# CameraSmartWatch.net
KiCad netlist of a schematic drawn in EasyEDA Pro
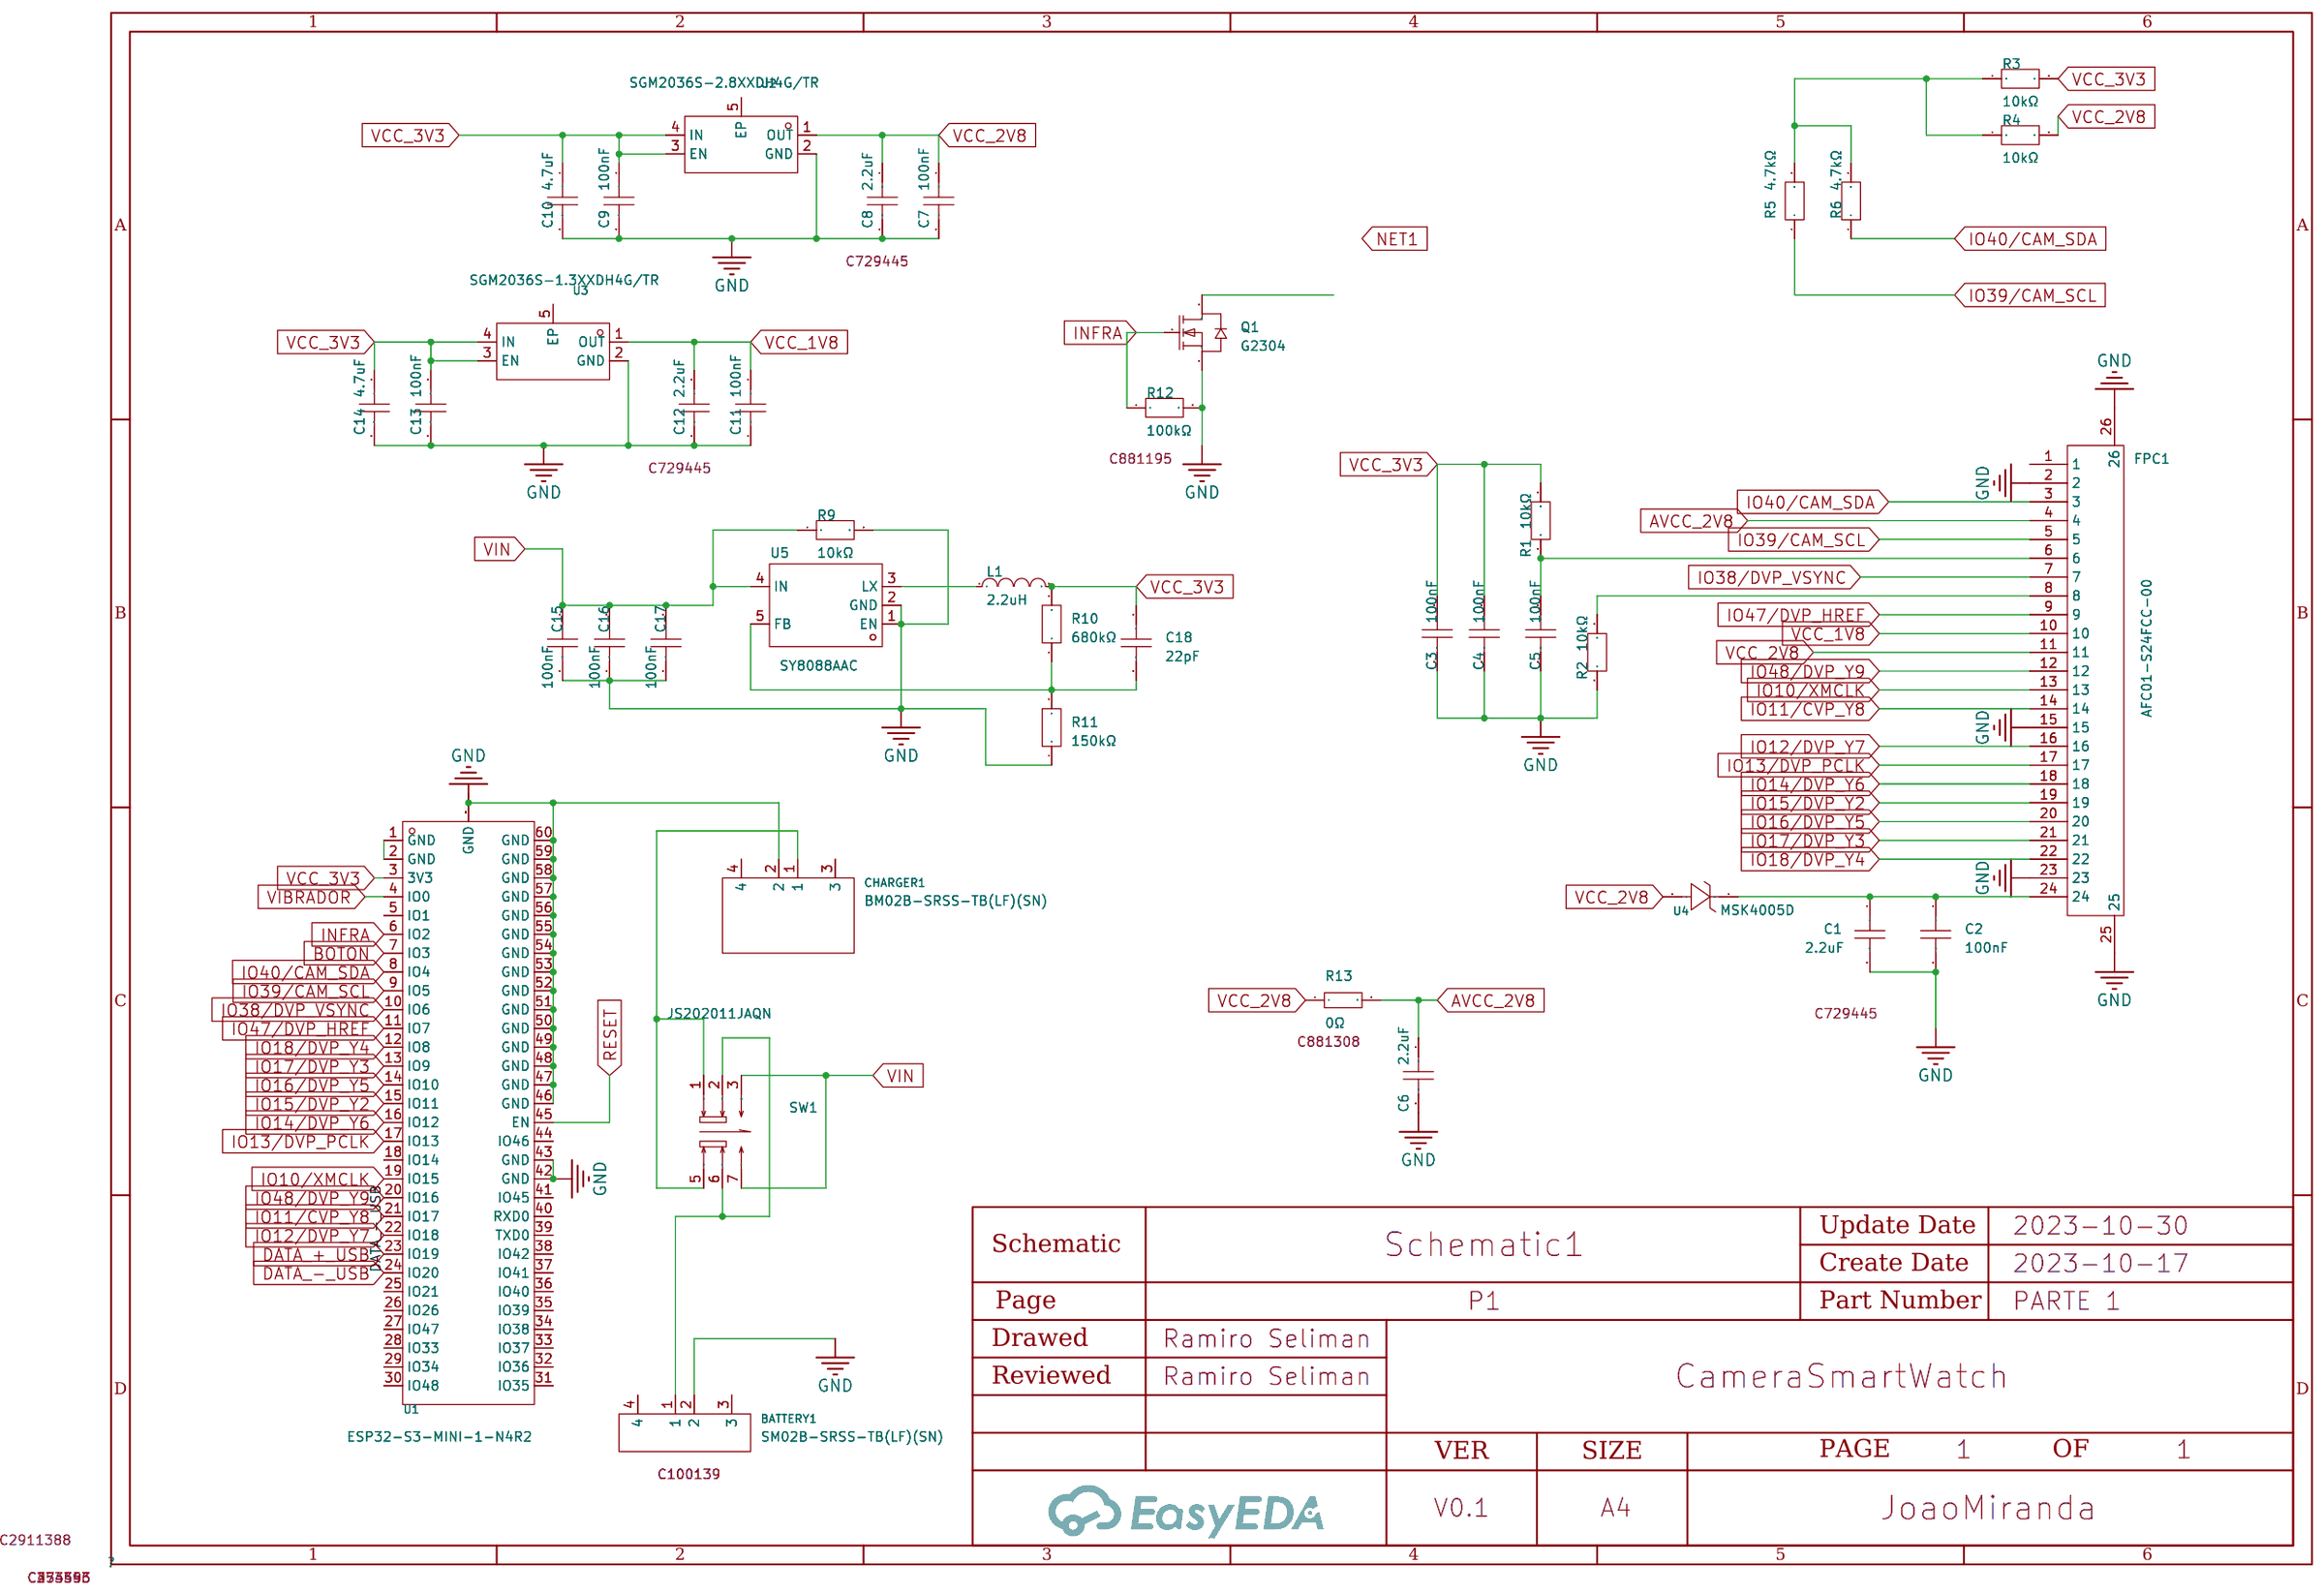
[diagram p0: schematic sheet]

(export (version "E")
  (design (tool "Eeschema 10.0.6"))
  (components
    (comp (ref "BATTERY1")
      (value "SM02B-SRSS-TB(LF)(SN)")
      (footprint "easyedapro:CONN-SMD_2P-P1.00_SM02B-SRSS-TB-LF-SN")
      (fields (field (name "Manufacturer") "JST"))
      (libsource (lib "easyedapro") (part "SM02B-SRSS-TB (LF)(SN)"))
    )
    (comp (ref "C1")
      (value "2.2uF")
      (footprint "easyedapro:C0201")
      (fields
        (field (name "Manufacturer Part") "C0201X5R225M100NT")
        (field (name "Manufacturer") "SANYEAR(叁叶源)")
        (field (name "Supplier Part") "C729445")
      )
      (libsource (lib "easyedapro") (part "CAP"))
    )
    (comp (ref "C2")
      (value "100nF")
      (footprint "easyedapro:C0201")
      (fields
        (field (name "Manufacturer Part") "C0201B104K016TSF")
        (field (name "Manufacturer") "IHHEC(禾伸堂)")
      )
      (libsource (lib "easyedapro") (part "CAP"))
    )
    (comp (ref "C3")
      (value "100nF")
      (footprint "easyedapro:C0201")
      (fields
        (field (name "Manufacturer Part") "C0201B104K016TSF")
        (field (name "Manufacturer") "IHHEC(禾伸堂)")
      )
      (libsource (lib "easyedapro") (part "CAP"))
    )
    (comp (ref "C4")
      (value "100nF")
      (footprint "easyedapro:C0201")
      (fields
        (field (name "Manufacturer Part") "C0201B104K016TSF")
        (field (name "Manufacturer") "IHHEC(禾伸堂)")
      )
      (libsource (lib "easyedapro") (part "CAP"))
    )
    (comp (ref "C5")
      (value "100nF")
      (footprint "easyedapro:C0201")
      (fields
        (field (name "Manufacturer Part") "C0201B104K016TSF")
        (field (name "Manufacturer") "IHHEC(禾伸堂)")
      )
      (libsource (lib "easyedapro") (part "CAP"))
    )
    (comp (ref "C6")
      (value "2.2uF")
      (footprint "easyedapro:C0201")
      (fields
        (field (name "Manufacturer Part") "C0201X5R225M100NT")
        (field (name "Manufacturer") "SANYEAR(叁叶源)")
      )
      (libsource (lib "easyedapro") (part "CAP"))
    )
    (comp (ref "C7")
      (value "100nF")
      (footprint "easyedapro:C0201")
      (fields
        (field (name "Manufacturer Part") "C0201B104K016TSF")
        (field (name "Manufacturer") "IHHEC(禾伸堂)")
      )
      (libsource (lib "easyedapro") (part "CAP"))
    )
    (comp (ref "C8")
      (value "2.2uF")
      (footprint "easyedapro:C0201")
      (fields
        (field (name "Manufacturer Part") "C0201X5R225M100NT")
        (field (name "Manufacturer") "SANYEAR(叁叶源)")
        (field (name "Supplier Part") "C729445")
      )
      (libsource (lib "easyedapro") (part "CAP"))
    )
    (comp (ref "C9")
      (value "100nF")
      (footprint "easyedapro:C0201")
      (fields
        (field (name "Manufacturer Part") "C0201B104K016TSF")
        (field (name "Manufacturer") "IHHEC(禾伸堂)")
      )
      (libsource (lib "easyedapro") (part "CAP"))
    )
    (comp (ref "C10")
      (value "4.7uF")
      (footprint "easyedapro:C0201")
      (fields
        (field (name "Manufacturer Part") "C0402X5R475M250NT")
        (field (name "Manufacturer") "SANYEAR(叁叶源)")
        (field (name "Supplier Part") "C2911388")
      )
      (libsource (lib "easyedapro") (part "CAP"))
    )
    (comp (ref "C11")
      (value "100nF")
      (footprint "easyedapro:C0201")
      (fields
        (field (name "Manufacturer Part") "C0201B104K016TSF")
        (field (name "Manufacturer") "IHHEC(禾伸堂)")
      )
      (libsource (lib "easyedapro") (part "CAP"))
    )
    (comp (ref "C12")
      (value "2.2uF")
      (footprint "easyedapro:C0201")
      (fields
        (field (name "Manufacturer Part") "C0201X5R225M100NT")
        (field (name "Manufacturer") "SANYEAR(叁叶源)")
        (field (name "Supplier Part") "C729445")
      )
      (libsource (lib "easyedapro") (part "CAP"))
    )
    (comp (ref "C13")
      (value "100nF")
      (footprint "easyedapro:C0201")
      (fields
        (field (name "Manufacturer Part") "C0201B104K016TSF")
        (field (name "Manufacturer") "IHHEC(禾伸堂)")
      )
      (libsource (lib "easyedapro") (part "CAP"))
    )
    (comp (ref "C14")
      (value "4.7uF")
      (footprint "easyedapro:C0201")
      (fields
        (field (name "Manufacturer Part") "C0402X5R475M250NT")
        (field (name "Manufacturer") "SANYEAR(叁叶源)")
        (field (name "Supplier Part") "C2911388")
      )
      (libsource (lib "easyedapro") (part "CAP"))
    )
    (comp (ref "C15")
      (value "100nF")
      (footprint "easyedapro:C0201")
      (fields
        (field (name "Manufacturer Part") "C0201B104K016TSF")
        (field (name "Manufacturer") "IHHEC(禾伸堂)")
      )
      (libsource (lib "easyedapro") (part "CAP"))
    )
    (comp (ref "C16")
      (value "100nF")
      (footprint "easyedapro:C0201")
      (fields
        (field (name "Manufacturer Part") "C0201B104K016TSF")
        (field (name "Manufacturer") "IHHEC(禾伸堂)")
      )
      (libsource (lib "easyedapro") (part "CAP"))
    )
    (comp (ref "C17")
      (value "100nF")
      (footprint "easyedapro:C0201")
      (fields
        (field (name "Manufacturer Part") "C0201B104K016TSF")
        (field (name "Manufacturer") "IHHEC(禾伸堂)")
      )
      (libsource (lib "easyedapro") (part "CAP"))
    )
    (comp (ref "C18")
      (value "22pF")
      (footprint "easyedapro:C0201")
      (fields
        (field (name "Manufacturer Part") "CC0201FRNPO8BN220")
        (field (name "Manufacturer") "YAGEO(国巨)")
      )
      (libsource (lib "easyedapro") (part "CAP"))
    )
    (comp (ref "CHARGER1")
      (value "BM02B-SRSS-TB(LF)(SN)")
      (footprint "easyedapro:CONN-TH_BM02B-SRSS-TB-LF-SN")
      (fields (field (name "Manufacturer") "JST"))
      (libsource (lib "easyedapro") (part "BM02B-SRSS-TB (LF)(SN)"))
    )
    (comp (ref "FPC1")
      (value "AFC01-S24FCC-00")
      (footprint "easyedapro:FPC-SMD_P0.5-24P_FGS-XJ-H2.0")
      (fields (field (name "Manufacturer") "JS(钜硕电子)"))
      (libsource (lib "easyedapro") (part "AFC01-S24FCC-00"))
    )
    (comp (ref "L1")
      (value "2.2uH")
      (footprint "easyedapro:L0603")
      (fields
        (field (name "Manufacturer Part") "CKCS252012-2.2uH/N")
        (field (name "Manufacturer") "CENKER(岑科)")
        (field (name "Supplier Part") "C354553")
      )
      (libsource (lib "easyedapro") (part "电感"))
    )
    (comp (ref "Q1")
      (value "G2304")
      (footprint "easyedapro:SOT-23-3_L2.9-W1.3-P1.90-LS2.4-BR")
      (fields (field (name "Manufacturer") "GOFORD(谷峰)"))
      (libsource (lib "easyedapro") (part "G2304"))
    )
    (comp (ref "R1")
      (value "10kΩ")
      (footprint "easyedapro:R0603")
      (description "Type: Resistance: Tolerance:±1% Tolerance:±1% Power(Watts):- Overload Voltage (Max):-")
      (fields (field (name "Manufacturer Part") "CR0201FH1002G") (field (name "Manufacturer") "LIZ(丽智电子)"))
      (libsource (lib "easyedapro") (part "CR0603F0R00P05Z"))
    )
    (comp (ref "R2")
      (value "10kΩ")
      (footprint "easyedapro:R0603")
      (description "Type: Resistance: Tolerance:±1% Tolerance:±1% Power(Watts):- Overload Voltage (Max):-")
      (fields (field (name "Manufacturer Part") "CR0201FH1002G") (field (name "Manufacturer") "LIZ(丽智电子)"))
      (libsource (lib "easyedapro") (part "CR0603F0R00P05Z"))
    )
    (comp (ref "R3")
      (value "10kΩ")
      (footprint "easyedapro:R0603")
      (description "Type: Resistance: Tolerance:±1% Tolerance:±1% Power(Watts):- Overload Voltage (Max):-")
      (fields (field (name "Manufacturer Part") "CR0201FH1002G") (field (name "Manufacturer") "LIZ(丽智电子)"))
      (libsource (lib "easyedapro") (part "CR0603F0R00P05Z"))
    )
    (comp (ref "R4")
      (value "10kΩ")
      (footprint "easyedapro:R0603")
      (description "Type: Resistance: Tolerance:±1% Tolerance:±1% Power(Watts):- Overload Voltage (Max):-")
      (fields (field (name "Manufacturer Part") "CR0201FH1002G") (field (name "Manufacturer") "LIZ(丽智电子)"))
      (libsource (lib "easyedapro") (part "CR0603F0R00P05Z"))
    )
    (comp (ref "R5")
      (value "4.7kΩ")
      (footprint "easyedapro:R0603")
      (fields
        (field (name "Manufacturer Part") "CR0201FH4701G")
        (field (name "Manufacturer") "LIZ(丽智电子)")
        (field (name "Supplier Part") "C100139")
      )
      (libsource (lib "easyedapro") (part "CR0603F0R00P05Z"))
    )
    (comp (ref "R6")
      (value "4.7kΩ")
      (footprint "easyedapro:R0603")
      (fields
        (field (name "Manufacturer Part") "CR0201FH4701G")
        (field (name "Manufacturer") "LIZ(丽智电子)")
        (field (name "Supplier Part") "C100139")
      )
      (libsource (lib "easyedapro") (part "CR0603F0R00P05Z"))
    )
    (comp (ref "R9")
      (value "10kΩ")
      (footprint "easyedapro:R0603")
      (description "Type: Resistance: Tolerance:±1% Tolerance:±1% Power(Watts):- Overload Voltage (Max):-")
      (fields (field (name "Manufacturer Part") "CR0201FH1002G") (field (name "Manufacturer") "LIZ(丽智电子)"))
      (libsource (lib "easyedapro") (part "CR0603F0R00P05Z"))
    )
    (comp (ref "R10")
      (value "680kΩ")
      (footprint "easyedapro:R0603")
      (fields
        (field (name "Manufacturer Part") "0201WMF6803TEE")
        (field (name "Manufacturer") "UNI-ROYAL(厚声)")
        (field (name "Supplier Part") "C473493")
      )
      (libsource (lib "easyedapro") (part "CR0603F0R00P05Z"))
    )
    (comp (ref "R11")
      (value "150kΩ")
      (footprint "easyedapro:R0603")
      (fields
        (field (name "Manufacturer Part") "RC0201FR-07150KL")
        (field (name "Manufacturer") "YAGEO(国巨)")
        (field (name "Supplier Part") "C274346")
      )
      (libsource (lib "easyedapro") (part "CR0603F0R00P05Z"))
    )
    (comp (ref "R12")
      (value "100kΩ")
      (footprint "easyedapro:R0603")
      (fields
        (field (name "Manufacturer Part") "CR0201J100KQ15Z")
        (field (name "Manufacturer") "EVER OHMS(天二科技)")
        (field (name "Supplier Part") "C881195")
      )
      (libsource (lib "easyedapro") (part "CR0603F0R00P05Z"))
    )
    (comp (ref "R13")
      (value "0Ω")
      (footprint "easyedapro:R0603")
      (fields
        (field (name "Manufacturer Part") "CR0603F0R00P05Z")
        (field (name "Manufacturer") "EVER OHMS(天二科技)")
        (field (name "Supplier Part") "C881308")
      )
      (libsource (lib "easyedapro") (part "Res"))
    )
    (comp (ref "SW1")
      (value "JS202011JAQN")
      (footprint "easyedapro:SW-SMD_JS202011JAQN")
      (fields (field (name "Manufacturer") "C&K"))
      (libsource (lib "easyedapro") (part "JS202011JAQN"))
    )
    (comp (ref "U1")
      (value "ESP32-S3-MINI-1-N4R2")
      (footprint "easyedapro:BULETM-SMD_ESP32-S3-MINI-1-N8")
      (fields (field (name "Manufacturer") "ESPRESSIF(乐鑫)"))
      (libsource (lib "easyedapro") (part "ESP32-S3-MINI-1-N4R2"))
    )
    (comp (ref "U2")
      (value "SGM2036S-2.8XXDH4G/TR")
      (footprint "easyedapro:USPQ-4B04_L1.0-W1.0-P0.65-BL-EP")
      (fields (field (name "Manufacturer") "SGMICRO(圣邦微)"))
      (libsource (lib "easyedapro") (part "SGM2036S-2.8XXDH4G/TR"))
    )
    (comp (ref "U3")
      (value "SGM2036S-1.3XXDH4G/TR")
      (footprint "easyedapro:USPQ-4B04_L1.0-W1.0-P0.65-BL-EP")
      (fields (field (name "Manufacturer") "SGMICRO(圣邦微)"))
      (libsource (lib "easyedapro") (part "SGM2036S-2.8XXDH4G/TR"))
    )
    (comp (ref "U4")
      (value "MSK4005D")
      (footprint "easyedapro:SOD-882_L1.0-W0.6-RD")
      (fields (field (name "Manufacturer") "SHIKUES(时科)"))
      (libsource (lib "easyedapro") (part "MSK4005D"))
    )
    (comp (ref "U5")
      (value "SY8088AAC")
      (footprint "easyedapro:SOT-23-5_L3.0-W1.7-P0.95-LS2.8-BR")
      (fields (field (name "Manufacturer") "silergy(矽力杰)"))
      (libsource (lib "easyedapro") (part "SY8088AAC"))
    )
  )
  (nets
    (net (code "1") (name "AVCC_2V8") (class "Default")
      (node (ref "C6") (pin "1") (pinfunction "1_1") (pintype "input"))
      (node (ref "FPC1") (pin "4") (pinfunction "4_4") (pintype "input"))
      (node (ref "R13") (pin "2") (pinfunction "2_2") (pintype "input"))
    )
    (net (code "2") (name "BOTON") (class "Default")
      (node (ref "U1") (pin "7") (pinfunction "IO3_7") (pintype "input"))
    )
    (net (code "3") (name "DATA_+_USB") (class "Default")
      (node (ref "U1") (pin "23") (pinfunction "IO19_23") (pintype "input"))
    )
    (net (code "4") (name "DATA_-_USB") (class "Default")
      (node (ref "U1") (pin "24") (pinfunction "IO20_24") (pintype "input"))
    )
    (net (code "5") (name "GND") (class "Default")
      (node (ref "BATTERY1") (pin "2") (pinfunction "2_2") (pintype "input"))
      (node (ref "C1") (pin "2") (pinfunction "2_2") (pintype "input"))
      (node (ref "C10") (pin "2") (pinfunction "2_2") (pintype "input"))
      (node (ref "C11") (pin "2") (pinfunction "2_2") (pintype "input"))
      (node (ref "C12") (pin "2") (pinfunction "2_2") (pintype "input"))
      (node (ref "C13") (pin "2") (pinfunction "2_2") (pintype "input"))
      (node (ref "C14") (pin "2") (pinfunction "2_2") (pintype "input"))
      (node (ref "C15") (pin "2") (pinfunction "2_2") (pintype "input"))
      (node (ref "C16") (pin "1") (pinfunction "1_1") (pintype "input"))
      (node (ref "C17") (pin "1") (pinfunction "1_1") (pintype "input"))
      (node (ref "C2") (pin "2") (pinfunction "2_2") (pintype "input"))
      (node (ref "C3") (pin "2") (pinfunction "2_2") (pintype "input"))
      (node (ref "C4") (pin "2") (pinfunction "2_2") (pintype "input"))
      (node (ref "C5") (pin "2") (pinfunction "2_2") (pintype "input"))
      (node (ref "C6") (pin "2") (pinfunction "2_2") (pintype "input"))
      (node (ref "C7") (pin "2") (pinfunction "2_2") (pintype "input"))
      (node (ref "C8") (pin "2") (pinfunction "2_2") (pintype "input"))
      (node (ref "C9") (pin "2") (pinfunction "2_2") (pintype "input"))
      (node (ref "CHARGER1") (pin "2") (pinfunction "2_2") (pintype "input"))
      (node (ref "FPC1") (pin "15") (pinfunction "15_15") (pintype "input"))
      (node (ref "FPC1") (pin "2") (pinfunction "2_2") (pintype "input"))
      (node (ref "FPC1") (pin "23") (pinfunction "23_23") (pintype "input"))
      (node (ref "FPC1") (pin "25") (pinfunction "25_25") (pintype "input"))
      (node (ref "FPC1") (pin "26") (pinfunction "26_26") (pintype "input"))
      (node (ref "Q1") (pin "2") (pinfunction "S_2") (pintype "input"))
      (node (ref "R11") (pin "1") (pinfunction "1_1") (pintype "input"))
      (node (ref "R12") (pin "2") (pinfunction "2_2") (pintype "input"))
      (node (ref "R2") (pin "1") (pinfunction "1_1") (pintype "input"))
      (node (ref "R9") (pin "2") (pinfunction "2_2") (pintype "input"))
      (node (ref "U1") (pin "42") (pinfunction "GND_42") (pintype "input"))
      (node (ref "U1") (pin "43") (pinfunction "GND_43") (pintype "input"))
      (node (ref "U1") (pin "46") (pinfunction "GND_46") (pintype "input"))
      (node (ref "U1") (pin "47") (pinfunction "GND_47") (pintype "input"))
      (node (ref "U1") (pin "48") (pinfunction "GND_48") (pintype "input"))
      (node (ref "U1") (pin "49") (pinfunction "GND_49") (pintype "input"))
      (node (ref "U1") (pin "50") (pinfunction "GND_50") (pintype "input"))
      (node (ref "U1") (pin "51") (pinfunction "GND_51") (pintype "input"))
      (node (ref "U1") (pin "52") (pinfunction "GND_52") (pintype "input"))
      (node (ref "U1") (pin "53") (pinfunction "GND_53") (pintype "input"))
      (node (ref "U1") (pin "54") (pinfunction "GND_54") (pintype "input"))
      (node (ref "U1") (pin "55") (pinfunction "GND_55") (pintype "input"))
      (node (ref "U1") (pin "56") (pinfunction "GND_56") (pintype "input"))
      (node (ref "U1") (pin "57") (pinfunction "GND_57") (pintype "input"))
      (node (ref "U1") (pin "58") (pinfunction "GND_58") (pintype "input"))
      (node (ref "U1") (pin "59") (pinfunction "GND_59") (pintype "input"))
      (node (ref "U1") (pin "60") (pinfunction "GND_60") (pintype "input"))
      (node (ref "U1") (pin "GND") (pinfunction "GND_GND") (pintype "input"))
      (node (ref "U2") (pin "2") (pinfunction "GND_2") (pintype "input"))
      (node (ref "U3") (pin "2") (pinfunction "GND_2") (pintype "input"))
      (node (ref "U5") (pin "1") (pinfunction "EN_1") (pintype "input"))
      (node (ref "U5") (pin "2") (pinfunction "GND_2") (pintype "input"))
    )
    (net (code "6") (name "INFRA") (class "Default")
      (node (ref "Q1") (pin "1") (pinfunction "G_1") (pintype "input"))
      (node (ref "R12") (pin "1") (pinfunction "1_1") (pintype "input"))
      (node (ref "U1") (pin "6") (pinfunction "IO2_6") (pintype "input"))
    )
    (net (code "7") (name "IO10{slash}XMCLK") (class "Default")
      (node (ref "FPC1") (pin "13") (pinfunction "13_13") (pintype "input"))
      (node (ref "U1") (pin "19") (pinfunction "IO15_19") (pintype "input"))
    )
    (net (code "8") (name "IO11{slash}CVP_Y8") (class "Default")
      (node (ref "FPC1") (pin "14") (pinfunction "14_14") (pintype "input"))
      (node (ref "U1") (pin "21") (pinfunction "IO17_21") (pintype "input"))
    )
    (net (code "9") (name "IO12{slash}DVP_Y7") (class "Default")
      (node (ref "FPC1") (pin "16") (pinfunction "16_16") (pintype "input"))
      (node (ref "U1") (pin "22") (pinfunction "IO18_22") (pintype "input"))
    )
    (net (code "10") (name "IO13{slash}DVP_PCLK") (class "Default")
      (node (ref "FPC1") (pin "17") (pinfunction "17_17") (pintype "input"))
      (node (ref "U1") (pin "17") (pinfunction "IO13_17") (pintype "input"))
    )
    (net (code "11") (name "IO14{slash}DVP_Y6") (class "Default")
      (node (ref "FPC1") (pin "18") (pinfunction "18_18") (pintype "input"))
      (node (ref "U1") (pin "16") (pinfunction "IO12_16") (pintype "input"))
    )
    (net (code "12") (name "IO15{slash}DVP_Y2") (class "Default")
      (node (ref "FPC1") (pin "19") (pinfunction "19_19") (pintype "input"))
      (node (ref "U1") (pin "15") (pinfunction "IO11_15") (pintype "input"))
    )
    (net (code "13") (name "IO16{slash}DVP_Y5") (class "Default")
      (node (ref "FPC1") (pin "20") (pinfunction "20_20") (pintype "input"))
      (node (ref "U1") (pin "14") (pinfunction "IO10_14") (pintype "input"))
    )
    (net (code "14") (name "IO17{slash}DVP_Y3") (class "Default")
      (node (ref "FPC1") (pin "21") (pinfunction "21_21") (pintype "input"))
      (node (ref "U1") (pin "13") (pinfunction "IO9_13") (pintype "input"))
    )
    (net (code "15") (name "IO18{slash}DVP_Y4") (class "Default")
      (node (ref "FPC1") (pin "22") (pinfunction "22_22") (pintype "input"))
      (node (ref "U1") (pin "12") (pinfunction "IO8_12") (pintype "input"))
    )
    (net (code "16") (name "IO38{slash}DVP_VSYNC") (class "Default")
      (node (ref "FPC1") (pin "7") (pinfunction "7_7") (pintype "input"))
      (node (ref "U1") (pin "10") (pinfunction "IO6_10") (pintype "input"))
    )
    (net (code "17") (name "IO39{slash}CAM_SCL") (class "Default")
      (node (ref "FPC1") (pin "5") (pinfunction "5_5") (pintype "input"))
      (node (ref "R5") (pin "1") (pinfunction "1_1") (pintype "input"))
      (node (ref "U1") (pin "9") (pinfunction "IO5_9") (pintype "input"))
    )
    (net (code "18") (name "IO40{slash}CAM_SDA") (class "Default")
      (node (ref "FPC1") (pin "3") (pinfunction "3_3") (pintype "input"))
      (node (ref "R6") (pin "1") (pinfunction "1_1") (pintype "input"))
      (node (ref "U1") (pin "8") (pinfunction "IO4_8") (pintype "input"))
    )
    (net (code "19") (name "IO47{slash}DVP_HREF") (class "Default")
      (node (ref "FPC1") (pin "9") (pinfunction "9_9") (pintype "input"))
      (node (ref "U1") (pin "11") (pinfunction "IO7_11") (pintype "input"))
    )
    (net (code "20") (name "IO48{slash}DVP_Y9") (class "Default")
      (node (ref "FPC1") (pin "12") (pinfunction "12_12") (pintype "input"))
      (node (ref "U1") (pin "20") (pinfunction "IO16_20") (pintype "input"))
    )
    (net (code "22") (name "Net-(BATTERY1-Pad1)") (class "Default")
      (node (ref "BATTERY1") (pin "1") (pinfunction "1_1") (pintype "input"))
      (node (ref "SW1") (pin "2") (pinfunction "2_2") (pintype "input"))
      (node (ref "SW1") (pin "6") (pinfunction "6_6") (pintype "input"))
    )
    (net (code "23") (name "Net-(C5-Pad1)") (class "Default")
      (node (ref "C5") (pin "1") (pinfunction "1_1") (pintype "input"))
      (node (ref "FPC1") (pin "6") (pinfunction "6_6") (pintype "input"))
      (node (ref "R1") (pin "1") (pinfunction "1_1") (pintype "input"))
    )
    (net (code "24") (name "Net-(CHARGER1-Pad1)") (class "Default")
      (node (ref "CHARGER1") (pin "1") (pinfunction "1_1") (pintype "input"))
      (node (ref "SW1") (pin "1") (pinfunction "1_1") (pintype "input"))
      (node (ref "SW1") (pin "5") (pinfunction "5_5") (pintype "input"))
    )
    (net (code "25") (name "Net-(FPC1-Pad8)") (class "Default")
      (node (ref "FPC1") (pin "8") (pinfunction "8_8") (pintype "input"))
      (node (ref "R2") (pin "2") (pinfunction "2_2") (pintype "input"))
    )
    (net (code "26") (name "Net-(R3-Pad1)") (class "Default")
      (node (ref "R3") (pin "1") (pinfunction "1_1") (pintype "input"))
      (node (ref "R4") (pin "1") (pinfunction "1_1") (pintype "input"))
      (node (ref "R5") (pin "2") (pinfunction "2_2") (pintype "input"))
      (node (ref "R6") (pin "2") (pinfunction "2_2") (pintype "input"))
    )
    (net (code "27") (name "Net-(U1-GND-Pad1)") (class "Default")
      (node (ref "U1") (pin "1") (pinfunction "GND_1") (pintype "input"))
      (node (ref "U1") (pin "2") (pinfunction "GND_2") (pintype "input"))
    )
    (net (code "28") (name "Net-(U4-K)") (class "Default")
      (node (ref "C1") (pin "1") (pinfunction "1_1") (pintype "input"))
      (node (ref "C2") (pin "1") (pinfunction "1_1") (pintype "input"))
      (node (ref "FPC1") (pin "24") (pinfunction "24_24") (pintype "input"))
      (node (ref "U4") (pin "1") (pinfunction "K_1") (pintype "input"))
    )
    (net (code "29") (name "Net-(U5-FB)") (class "Default")
      (node (ref "C18") (pin "2") (pinfunction "2_2") (pintype "input"))
      (node (ref "R10") (pin "1") (pinfunction "1_1") (pintype "input"))
      (node (ref "R11") (pin "2") (pinfunction "2_2") (pintype "input"))
      (node (ref "U5") (pin "5") (pinfunction "FB_5") (pintype "input"))
    )
    (net (code "30") (name "Net-(U5-LX)") (class "Default")
      (node (ref "L1") (pin "1") (pinfunction "1_1") (pintype "input"))
      (node (ref "U5") (pin "3") (pinfunction "LX_3") (pintype "input"))
    )
    (net (code "31") (name "RESET") (class "Default")
      (node (ref "U1") (pin "45") (pinfunction "EN_45") (pintype "input"))
    )
    (net (code "32") (name "VCC_1V8") (class "Default")
      (node (ref "C11") (pin "1") (pinfunction "1_1") (pintype "input"))
      (node (ref "C12") (pin "1") (pinfunction "1_1") (pintype "input"))
      (node (ref "FPC1") (pin "10") (pinfunction "10_10") (pintype "input"))
      (node (ref "U3") (pin "1") (pinfunction "OUT_1") (pintype "input"))
    )
    (net (code "33") (name "VCC_2V8") (class "Default")
      (node (ref "C7") (pin "1") (pinfunction "1_1") (pintype "input"))
      (node (ref "C8") (pin "1") (pinfunction "1_1") (pintype "input"))
      (node (ref "FPC1") (pin "11") (pinfunction "11_11") (pintype "input"))
      (node (ref "R13") (pin "1") (pinfunction "1_1") (pintype "input"))
      (node (ref "R4") (pin "2") (pinfunction "2_2") (pintype "input"))
      (node (ref "U2") (pin "1") (pinfunction "OUT_1") (pintype "input"))
      (node (ref "U4") (pin "2") (pinfunction "A_2") (pintype "input"))
    )
    (net (code "34") (name "VCC_3V3") (class "Default")
      (node (ref "C10") (pin "1") (pinfunction "1_1") (pintype "input"))
      (node (ref "C13") (pin "1") (pinfunction "1_1") (pintype "input"))
      (node (ref "C14") (pin "1") (pinfunction "1_1") (pintype "input"))
      (node (ref "C18") (pin "1") (pinfunction "1_1") (pintype "input"))
      (node (ref "C3") (pin "1") (pinfunction "1_1") (pintype "input"))
      (node (ref "C4") (pin "1") (pinfunction "1_1") (pintype "input"))
      (node (ref "C9") (pin "1") (pinfunction "1_1") (pintype "input"))
      (node (ref "L1") (pin "2") (pinfunction "2_2") (pintype "input"))
      (node (ref "R1") (pin "2") (pinfunction "2_2") (pintype "input"))
      (node (ref "R10") (pin "2") (pinfunction "2_2") (pintype "input"))
      (node (ref "R3") (pin "2") (pinfunction "2_2") (pintype "input"))
      (node (ref "U1") (pin "3") (pinfunction "3V3_3") (pintype "input"))
      (node (ref "U2") (pin "3") (pinfunction "EN_3") (pintype "input"))
      (node (ref "U2") (pin "4") (pinfunction "IN_4") (pintype "input"))
      (node (ref "U3") (pin "3") (pinfunction "EN_3") (pintype "input"))
      (node (ref "U3") (pin "4") (pinfunction "IN_4") (pintype "input"))
    )
    (net (code "35") (name "VIBRADOR") (class "Default")
      (node (ref "U1") (pin "4") (pinfunction "IO0_4") (pintype "input"))
    )
    (net (code "36") (name "VIN") (class "Default")
      (node (ref "C15") (pin "1") (pinfunction "1_1") (pintype "input"))
      (node (ref "C16") (pin "2") (pinfunction "2_2") (pintype "input"))
      (node (ref "C17") (pin "2") (pinfunction "2_2") (pintype "input"))
      (node (ref "R9") (pin "1") (pinfunction "1_1") (pintype "input"))
      (node (ref "SW1") (pin "3") (pinfunction "3_3") (pintype "input"))
      (node (ref "SW1") (pin "7") (pinfunction "7_7") (pintype "input"))
      (node (ref "U5") (pin "4") (pinfunction "IN_4") (pintype "input"))
    )
    (net (code "37") (name "unconnected-(BATTERY1-Pad3)") (class "Default")
      (node (ref "BATTERY1") (pin "3") (pinfunction "3_3") (pintype "input"))
    )
    (net (code "38") (name "unconnected-(BATTERY1-Pad4)") (class "Default")
      (node (ref "BATTERY1") (pin "4") (pinfunction "4_4") (pintype "input"))
    )
    (net (code "39") (name "unconnected-(CHARGER1-Pad3)") (class "Default")
      (node (ref "CHARGER1") (pin "3") (pinfunction "3_3") (pintype "input"))
    )
    (net (code "40") (name "unconnected-(CHARGER1-Pad4)") (class "Default")
      (node (ref "CHARGER1") (pin "4") (pinfunction "4_4") (pintype "input"))
    )
    (net (code "41") (name "unconnected-(FPC1-Pad1)") (class "Default")
      (node (ref "FPC1") (pin "1") (pinfunction "1_1") (pintype "input"))
    )
    (net (code "42") (name "unconnected-(Q1-D-Pad3)") (class "Default")
      (node (ref "Q1") (pin "3") (pinfunction "D_3") (pintype "input"))
    )
    (net (code "43") (name "unconnected-(U1-IO1-Pad5)") (class "Default")
      (node (ref "U1") (pin "5") (pinfunction "IO1_5") (pintype "input"))
    )
    (net (code "44") (name "unconnected-(U1-IO14-Pad18)") (class "Default")
      (node (ref "U1") (pin "18") (pinfunction "IO14_18") (pintype "input"))
    )
    (net (code "45") (name "unconnected-(U1-IO21-Pad25)") (class "Default")
      (node (ref "U1") (pin "25") (pinfunction "IO21_25") (pintype "input"))
    )
    (net (code "46") (name "unconnected-(U1-IO26-Pad26)") (class "Default")
      (node (ref "U1") (pin "26") (pinfunction "IO26_26") (pintype "input"))
    )
    (net (code "47") (name "unconnected-(U1-IO33-Pad28)") (class "Default")
      (node (ref "U1") (pin "28") (pinfunction "IO33_28") (pintype "input"))
    )
    (net (code "48") (name "unconnected-(U1-IO34-Pad29)") (class "Default")
      (node (ref "U1") (pin "29") (pinfunction "IO34_29") (pintype "input"))
    )
    (net (code "49") (name "unconnected-(U1-IO35-Pad31)") (class "Default")
      (node (ref "U1") (pin "31") (pinfunction "IO35_31") (pintype "input"))
    )
    (net (code "50") (name "unconnected-(U1-IO36-Pad32)") (class "Default")
      (node (ref "U1") (pin "32") (pinfunction "IO36_32") (pintype "input"))
    )
    (net (code "51") (name "unconnected-(U1-IO37-Pad33)") (class "Default")
      (node (ref "U1") (pin "33") (pinfunction "IO37_33") (pintype "input"))
    )
    (net (code "52") (name "unconnected-(U1-IO38-Pad34)") (class "Default")
      (node (ref "U1") (pin "34") (pinfunction "IO38_34") (pintype "input"))
    )
    (net (code "53") (name "unconnected-(U1-IO39-Pad35)") (class "Default")
      (node (ref "U1") (pin "35") (pinfunction "IO39_35") (pintype "input"))
    )
    (net (code "54") (name "unconnected-(U1-IO40-Pad36)") (class "Default")
      (node (ref "U1") (pin "36") (pinfunction "IO40_36") (pintype "input"))
    )
    (net (code "55") (name "unconnected-(U1-IO41-Pad37)") (class "Default")
      (node (ref "U1") (pin "37") (pinfunction "IO41_37") (pintype "input"))
    )
    (net (code "56") (name "unconnected-(U1-IO42-Pad38)") (class "Default")
      (node (ref "U1") (pin "38") (pinfunction "IO42_38") (pintype "input"))
    )
    (net (code "57") (name "unconnected-(U1-IO45-Pad41)") (class "Default")
      (node (ref "U1") (pin "41") (pinfunction "IO45_41") (pintype "input"))
    )
    (net (code "58") (name "unconnected-(U1-IO46-Pad44)") (class "Default")
      (node (ref "U1") (pin "44") (pinfunction "IO46_44") (pintype "input"))
    )
    (net (code "59") (name "unconnected-(U1-IO47-Pad27)") (class "Default")
      (node (ref "U1") (pin "27") (pinfunction "IO47_27") (pintype "input"))
    )
    (net (code "60") (name "unconnected-(U1-IO48-Pad30)") (class "Default")
      (node (ref "U1") (pin "30") (pinfunction "IO48_30") (pintype "input"))
    )
    (net (code "61") (name "unconnected-(U1-RXD0-Pad40)") (class "Default")
      (node (ref "U1") (pin "40") (pinfunction "RXD0_40") (pintype "input"))
    )
    (net (code "62") (name "unconnected-(U1-TXD0-Pad39)") (class "Default")
      (node (ref "U1") (pin "39") (pinfunction "TXD0_39") (pintype "input"))
    )
    (net (code "63") (name "unconnected-(U2-EP-Pad5)") (class "Default")
      (node (ref "U2") (pin "5") (pinfunction "EP_5") (pintype "input"))
    )
    (net (code "64") (name "unconnected-(U3-EP-Pad5)") (class "Default")
      (node (ref "U3") (pin "5") (pinfunction "EP_5") (pintype "input"))
    )
  )
)
